# X95840Shield.net
KiCad netlist of a schematic drawn in EAGLE
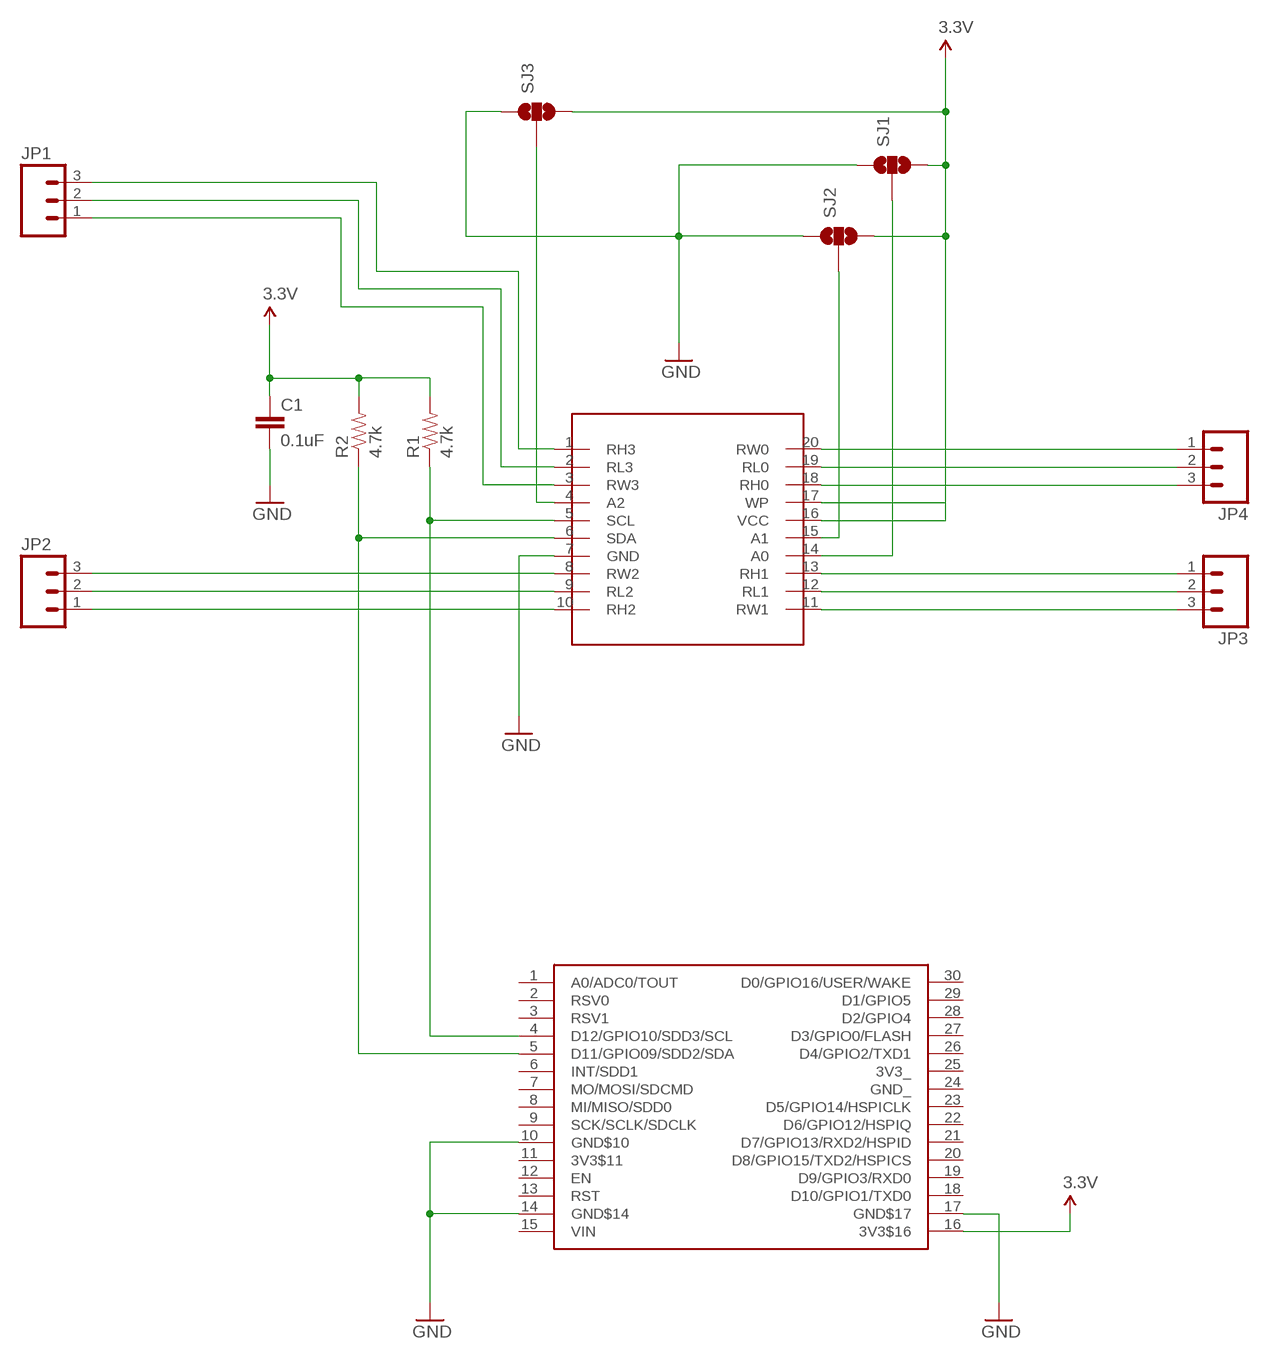
[diagram p0: schematic, sheet 1]

(export (version "E")
  (design (tool "Eeschema 10.0.6"))
  (components
    (comp (ref "C1")
      (value "0.1uF")
      (footprint "eagle-import:0402-CAP")
      (libsource (lib "eagle-import") (part "CAP0402-CAP"))
    )
    (comp (ref "JP1")
      (value "M03SCREW")
      (footprint "eagle-import:SCREWTERMINAL-3.5MM-3")
      (libsource (lib "eagle-import") (part "M03SCREW"))
    )
    (comp (ref "JP2")
      (value "M03SCREW")
      (footprint "eagle-import:SCREWTERMINAL-3.5MM-3")
      (libsource (lib "eagle-import") (part "M03SCREW"))
    )
    (comp (ref "JP3")
      (value "M03SCREW")
      (footprint "eagle-import:SCREWTERMINAL-3.5MM-3")
      (libsource (lib "eagle-import") (part "M03SCREW"))
    )
    (comp (ref "JP4")
      (value "M03SCREW")
      (footprint "eagle-import:SCREWTERMINAL-3.5MM-3")
      (libsource (lib "eagle-import") (part "M03SCREW"))
    )
    (comp (ref "R1")
      (value "4.7k")
      (footprint "eagle-import:0402-RES")
      (libsource (lib "eagle-import") (part "RESISTOR0402-RES"))
    )
    (comp (ref "R2")
      (value "4.7k")
      (footprint "eagle-import:0402-RES")
      (libsource (lib "eagle-import") (part "RESISTOR0402-RES"))
    )
    (comp (ref "SJ1")
      (value "SOLDERJUMPER_2WAYPASTE1&2")
      (footprint "eagle-import:SJ_3_PASTE1&2")
      (libsource (lib "eagle-import") (part "SOLDERJUMPER_2WAYPASTE1&2"))
    )
    (comp (ref "SJ2")
      (value "SOLDERJUMPER_2WAYPASTE1&2")
      (footprint "eagle-import:SJ_3_PASTE1&2")
      (libsource (lib "eagle-import") (part "SOLDERJUMPER_2WAYPASTE1&2"))
    )
    (comp (ref "SJ3")
      (value "SOLDERJUMPER_2WAYPASTE1&2")
      (footprint "eagle-import:SJ_3_PASTE1&2")
      (libsource (lib "eagle-import") (part "SOLDERJUMPER_2WAYPASTE1&2"))
    )
    (comp (ref "U$1")
      (value "NERDSHIELD")
      (footprint "eagle-import:NERDUINO_STACK")
      (libsource (lib "eagle-import") (part "NERDSHIELD"))
    )
    (comp (ref "U$3")
      (value "X95840")
      (footprint "eagle-import:TSSOP20")
      (libsource (lib "eagle-import") (part "X95840"))
    )
  )
  (nets
    (net (code "1") (name "3.3V") (class "Default")
      (node (ref "C1") (pin "1") (pinfunction "1_1") (pintype "passive"))
      (node (ref "R1") (pin "2") (pinfunction "2_2") (pintype "passive"))
      (node (ref "R2") (pin "2") (pinfunction "2_2") (pintype "passive"))
      (node (ref "SJ1") (pin "3") (pinfunction "3_3") (pintype "passive"))
      (node (ref "SJ2") (pin "3") (pinfunction "3_3") (pintype "passive"))
      (node (ref "SJ3") (pin "3") (pinfunction "3_3") (pintype "passive"))
      (node (ref "U$1") (pin "16") (pinfunction "3V3$16_16") (pintype "bidirectional"))
      (node (ref "U$3") (pin "16") (pinfunction "VCC_16") (pintype "bidirectional"))
      (node (ref "U$3") (pin "17") (pinfunction "WP_17") (pintype "bidirectional"))
    )
    (net (code "2") (name "GND") (class "Default")
      (node (ref "C1") (pin "2") (pinfunction "2_2") (pintype "passive"))
      (node (ref "SJ1") (pin "1") (pinfunction "1_1") (pintype "passive"))
      (node (ref "SJ2") (pin "1") (pinfunction "1_1") (pintype "passive"))
      (node (ref "SJ3") (pin "1") (pinfunction "1_1") (pintype "passive"))
      (node (ref "U$1") (pin "10") (pinfunction "GND$10_10") (pintype "bidirectional"))
      (node (ref "U$1") (pin "14") (pinfunction "GND$14_14") (pintype "bidirectional"))
      (node (ref "U$1") (pin "17") (pinfunction "GND$17_17") (pintype "bidirectional"))
      (node (ref "U$3") (pin "7") (pinfunction "GND_7") (pintype "bidirectional"))
    )
    (net (code "3") (name "Net-(U$1-D11{slash}GPIO09{slash}SDD2{slash}SDA)") (class "Default")
      (node (ref "R2") (pin "1") (pinfunction "1_1") (pintype "passive"))
      (node (ref "U$1") (pin "5") (pinfunction "D11/GPIO09/SDD2/SDA_5") (pintype "bidirectional"))
      (node (ref "U$3") (pin "6") (pinfunction "SDA_6") (pintype "bidirectional"))
    )
    (net (code "4") (name "Net-(U$1-D12{slash}GPIO10{slash}SDD3{slash}SCL)") (class "Default")
      (node (ref "R1") (pin "1") (pinfunction "1_1") (pintype "passive"))
      (node (ref "U$1") (pin "4") (pinfunction "D12/GPIO10/SDD3/SCL_4") (pintype "bidirectional"))
      (node (ref "U$3") (pin "5") (pinfunction "SCL_5") (pintype "bidirectional"))
    )
    (net (code "5") (name "Net-(U$3-A0)") (class "Default")
      (node (ref "SJ1") (pin "2") (pinfunction "2_2") (pintype "passive"))
      (node (ref "U$3") (pin "14") (pinfunction "A0_14") (pintype "bidirectional"))
    )
    (net (code "6") (name "Net-(U$3-A1)") (class "Default")
      (node (ref "SJ2") (pin "2") (pinfunction "2_2") (pintype "passive"))
      (node (ref "U$3") (pin "15") (pinfunction "A1_15") (pintype "bidirectional"))
    )
    (net (code "7") (name "Net-(U$3-A2)") (class "Default")
      (node (ref "SJ3") (pin "2") (pinfunction "2_2") (pintype "passive"))
      (node (ref "U$3") (pin "4") (pinfunction "A2_4") (pintype "bidirectional"))
    )
    (net (code "8") (name "Net-(U$3-RH0)") (class "Default")
      (node (ref "JP4") (pin "3") (pinfunction "3_3") (pintype "passive"))
      (node (ref "U$3") (pin "18") (pinfunction "RH0_18") (pintype "bidirectional"))
    )
    (net (code "9") (name "Net-(U$3-RH1)") (class "Default")
      (node (ref "JP3") (pin "1") (pinfunction "1_1") (pintype "passive"))
      (node (ref "U$3") (pin "13") (pinfunction "RH1_13") (pintype "bidirectional"))
    )
    (net (code "10") (name "Net-(U$3-RH2)") (class "Default")
      (node (ref "JP2") (pin "1") (pinfunction "1_1") (pintype "passive"))
      (node (ref "U$3") (pin "10") (pinfunction "RH2_10") (pintype "bidirectional"))
    )
    (net (code "11") (name "Net-(U$3-RH3)") (class "Default")
      (node (ref "JP1") (pin "3") (pinfunction "3_3") (pintype "passive"))
      (node (ref "U$3") (pin "1") (pinfunction "RH3_1") (pintype "bidirectional"))
    )
    (net (code "12") (name "Net-(U$3-RL0)") (class "Default")
      (node (ref "JP4") (pin "2") (pinfunction "2_2") (pintype "passive"))
      (node (ref "U$3") (pin "19") (pinfunction "RL0_19") (pintype "bidirectional"))
    )
    (net (code "13") (name "Net-(U$3-RL1)") (class "Default")
      (node (ref "JP3") (pin "2") (pinfunction "2_2") (pintype "passive"))
      (node (ref "U$3") (pin "12") (pinfunction "RL1_12") (pintype "bidirectional"))
    )
    (net (code "14") (name "Net-(U$3-RL2)") (class "Default")
      (node (ref "JP2") (pin "2") (pinfunction "2_2") (pintype "passive"))
      (node (ref "U$3") (pin "9") (pinfunction "RL2_9") (pintype "bidirectional"))
    )
    (net (code "15") (name "Net-(U$3-RL3)") (class "Default")
      (node (ref "JP1") (pin "2") (pinfunction "2_2") (pintype "passive"))
      (node (ref "U$3") (pin "2") (pinfunction "RL3_2") (pintype "bidirectional"))
    )
    (net (code "16") (name "Net-(U$3-RW0)") (class "Default")
      (node (ref "JP4") (pin "1") (pinfunction "1_1") (pintype "passive"))
      (node (ref "U$3") (pin "20") (pinfunction "RW0_20") (pintype "bidirectional"))
    )
    (net (code "17") (name "Net-(U$3-RW1)") (class "Default")
      (node (ref "JP3") (pin "3") (pinfunction "3_3") (pintype "passive"))
      (node (ref "U$3") (pin "11") (pinfunction "RW1_11") (pintype "bidirectional"))
    )
    (net (code "18") (name "Net-(U$3-RW2)") (class "Default")
      (node (ref "JP2") (pin "3") (pinfunction "3_3") (pintype "passive"))
      (node (ref "U$3") (pin "8") (pinfunction "RW2_8") (pintype "bidirectional"))
    )
    (net (code "19") (name "Net-(U$3-RW3)") (class "Default")
      (node (ref "JP1") (pin "1") (pinfunction "1_1") (pintype "passive"))
      (node (ref "U$3") (pin "3") (pinfunction "RW3_3") (pintype "bidirectional"))
    )
    (net (code "20") (name "unconnected-(U$1-3V3$11-Pad11)") (class "Default")
      (node (ref "U$1") (pin "11") (pinfunction "3V3$11_11") (pintype "bidirectional"))
    )
    (net (code "21") (name "unconnected-(U$1-3V3_-Pad25)") (class "Default")
      (node (ref "U$1") (pin "25") (pinfunction "3V3__25") (pintype "bidirectional"))
    )
    (net (code "22") (name "unconnected-(U$1-A0{slash}ADC0{slash}TOUT-Pad1)") (class "Default")
      (node (ref "U$1") (pin "1") (pinfunction "A0/ADC0/TOUT_1") (pintype "bidirectional"))
    )
    (net (code "23") (name "unconnected-(U$1-D0{slash}GPIO16{slash}USER{slash}WAKE-Pad30)") (class "Default")
      (node (ref "U$1") (pin "30") (pinfunction "D0/GPIO16/USER/WAKE_30") (pintype "bidirectional"))
    )
    (net (code "24") (name "unconnected-(U$1-D1{slash}GPIO5-Pad29)") (class "Default")
      (node (ref "U$1") (pin "29") (pinfunction "D1/GPIO5_29") (pintype "bidirectional"))
    )
    (net (code "25") (name "unconnected-(U$1-D2{slash}GPIO4-Pad28)") (class "Default")
      (node (ref "U$1") (pin "28") (pinfunction "D2/GPIO4_28") (pintype "bidirectional"))
    )
    (net (code "26") (name "unconnected-(U$1-D3{slash}GPIO0{slash}FLASH-Pad27)") (class "Default")
      (node (ref "U$1") (pin "27") (pinfunction "D3/GPIO0/FLASH_27") (pintype "bidirectional"))
    )
    (net (code "27") (name "unconnected-(U$1-D4{slash}GPIO2{slash}TXD1-Pad26)") (class "Default")
      (node (ref "U$1") (pin "26") (pinfunction "D4/GPIO2/TXD1_26") (pintype "bidirectional"))
    )
    (net (code "28") (name "unconnected-(U$1-D5{slash}GPIO14{slash}HSPICLK-Pad23)") (class "Default")
      (node (ref "U$1") (pin "23") (pinfunction "D5/GPIO14/HSPICLK_23") (pintype "bidirectional"))
    )
    (net (code "29") (name "unconnected-(U$1-D6{slash}GPIO12{slash}HSPIQ-Pad22)") (class "Default")
      (node (ref "U$1") (pin "22") (pinfunction "D6/GPIO12/HSPIQ_22") (pintype "bidirectional"))
    )
    (net (code "30") (name "unconnected-(U$1-D7{slash}GPIO13{slash}RXD2{slash}HSPID-Pad21)") (class "Default")
      (node (ref "U$1") (pin "21") (pinfunction "D7/GPIO13/RXD2/HSPID_21") (pintype "bidirectional"))
    )
    (net (code "31") (name "unconnected-(U$1-D8{slash}GPIO15{slash}TXD2{slash}HSPICS-Pad20)") (class "Default")
      (node (ref "U$1") (pin "20") (pinfunction "D8/GPIO15/TXD2/HSPICS_20") (pintype "bidirectional"))
    )
    (net (code "32") (name "unconnected-(U$1-D9{slash}GPIO3{slash}RXD0-Pad19)") (class "Default")
      (node (ref "U$1") (pin "19") (pinfunction "D9/GPIO3/RXD0_19") (pintype "bidirectional"))
    )
    (net (code "33") (name "unconnected-(U$1-D10{slash}GPIO1{slash}TXD0-Pad18)") (class "Default")
      (node (ref "U$1") (pin "18") (pinfunction "D10/GPIO1/TXD0_18") (pintype "bidirectional"))
    )
    (net (code "34") (name "unconnected-(U$1-EN-Pad12)") (class "Default")
      (node (ref "U$1") (pin "12") (pinfunction "EN_12") (pintype "bidirectional"))
    )
    (net (code "35") (name "unconnected-(U$1-GND_-Pad24)") (class "Default")
      (node (ref "U$1") (pin "24") (pinfunction "GND__24") (pintype "bidirectional"))
    )
    (net (code "36") (name "unconnected-(U$1-INT{slash}SDD1-Pad6)") (class "Default")
      (node (ref "U$1") (pin "6") (pinfunction "INT/SDD1_6") (pintype "bidirectional"))
    )
    (net (code "37") (name "unconnected-(U$1-MI{slash}MISO{slash}SDD0-Pad8)") (class "Default")
      (node (ref "U$1") (pin "8") (pinfunction "MI/MISO/SDD0_8") (pintype "bidirectional"))
    )
    (net (code "38") (name "unconnected-(U$1-MO{slash}MOSI{slash}SDCMD-Pad7)") (class "Default")
      (node (ref "U$1") (pin "7") (pinfunction "MO/MOSI/SDCMD_7") (pintype "bidirectional"))
    )
    (net (code "39") (name "unconnected-(U$1-RST-Pad13)") (class "Default")
      (node (ref "U$1") (pin "13") (pinfunction "RST_13") (pintype "bidirectional"))
    )
    (net (code "40") (name "unconnected-(U$1-RSV0-Pad2)") (class "Default")
      (node (ref "U$1") (pin "2") (pinfunction "RSV0_2") (pintype "bidirectional"))
    )
    (net (code "41") (name "unconnected-(U$1-RSV1-Pad3)") (class "Default")
      (node (ref "U$1") (pin "3") (pinfunction "RSV1_3") (pintype "bidirectional"))
    )
    (net (code "42") (name "unconnected-(U$1-SCK{slash}SCLK{slash}SDCLK-Pad9)") (class "Default")
      (node (ref "U$1") (pin "9") (pinfunction "SCK/SCLK/SDCLK_9") (pintype "bidirectional"))
    )
    (net (code "43") (name "unconnected-(U$1-VIN-Pad15)") (class "Default")
      (node (ref "U$1") (pin "15") (pinfunction "VIN_15") (pintype "bidirectional"))
    )
  )
)
